# Top.net
KiCad netlist of a schematic drawn in Altium Designer
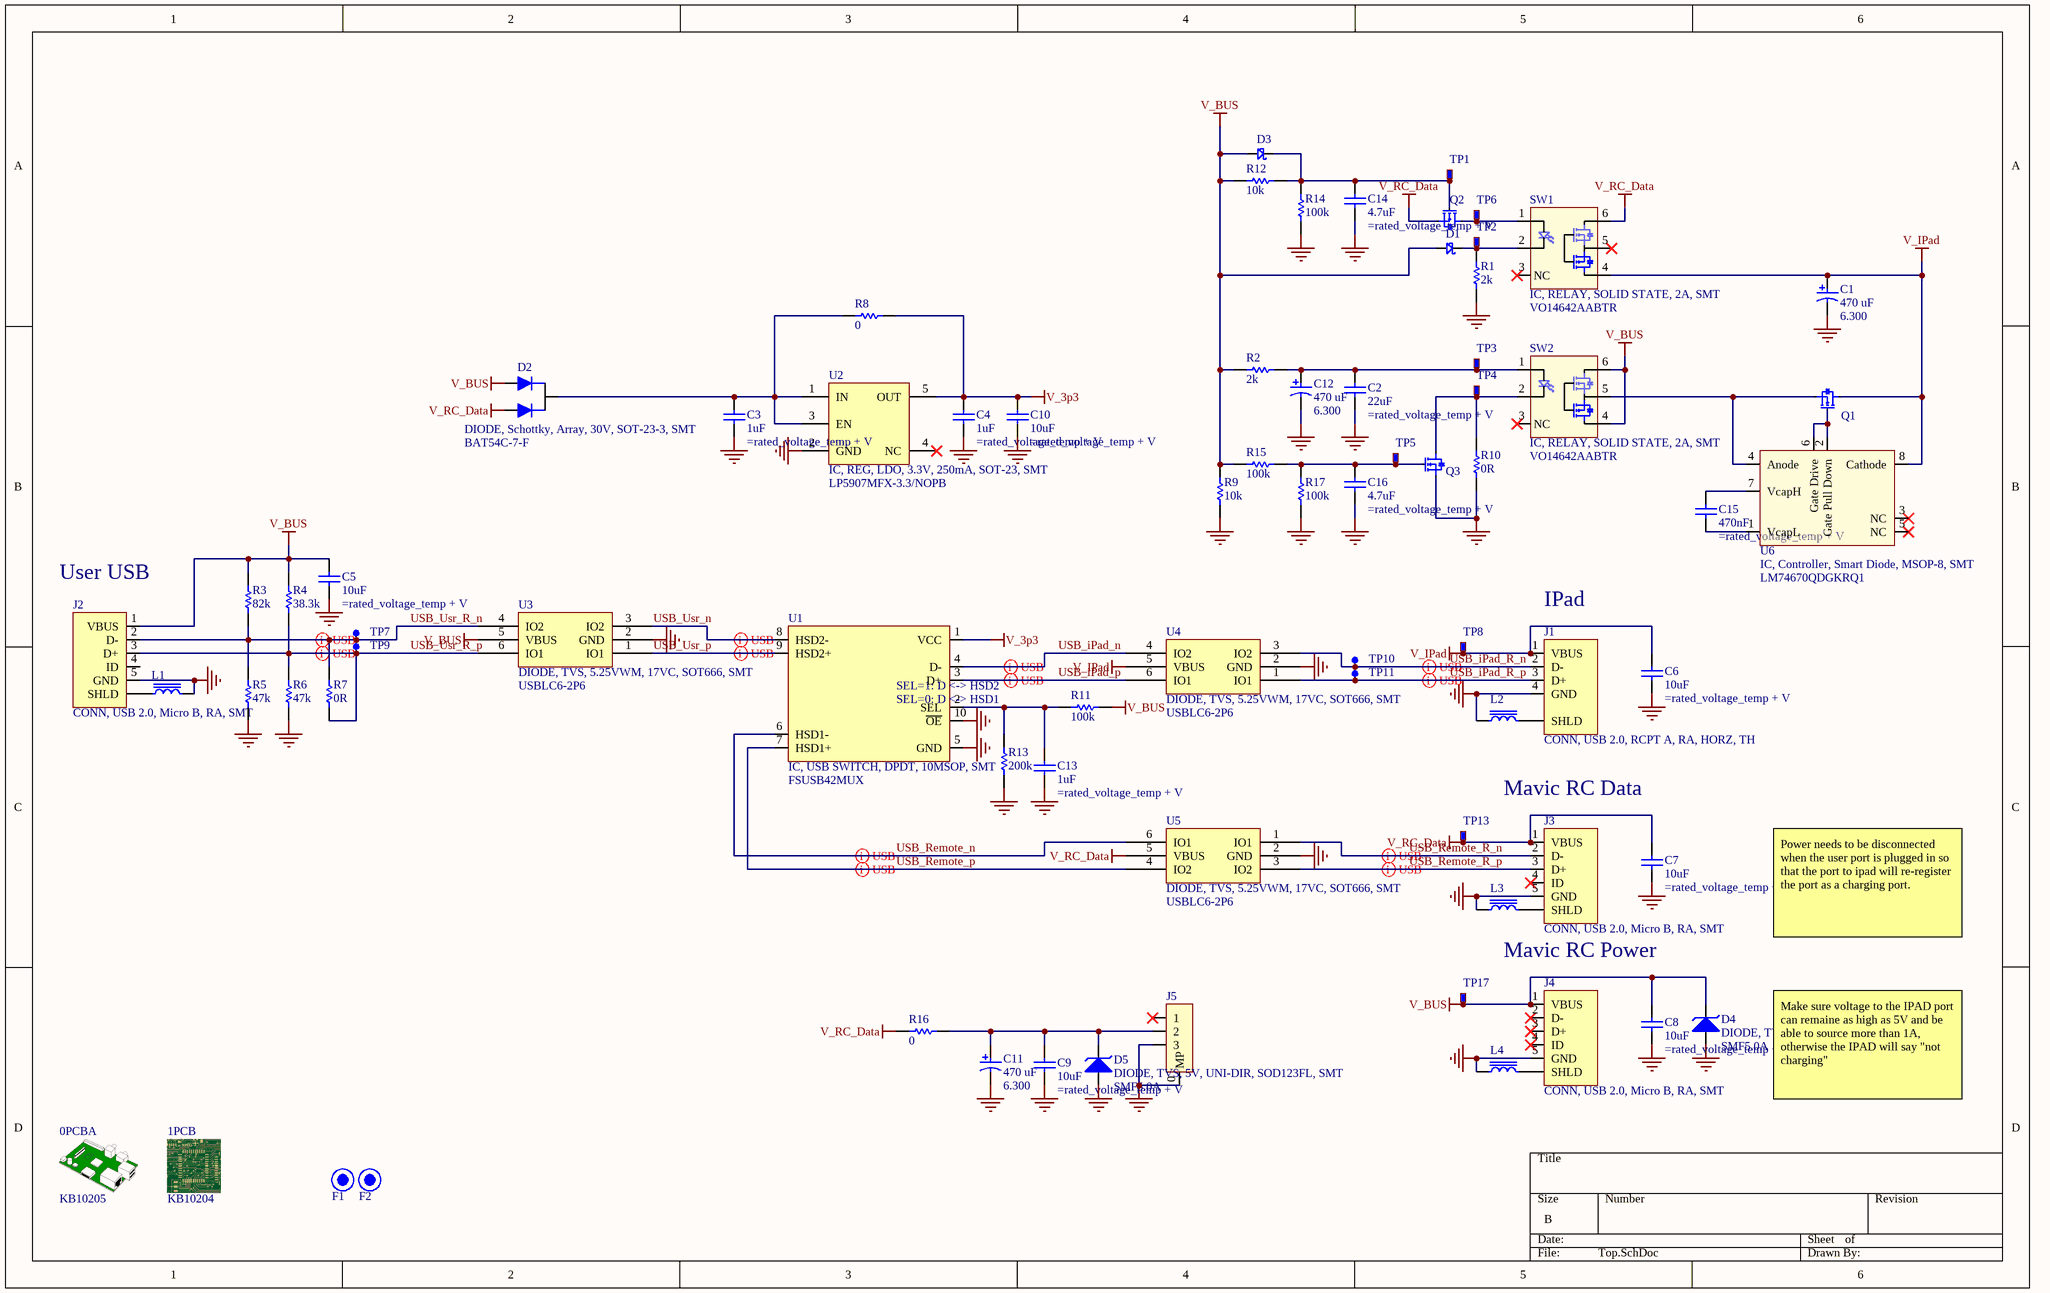
[diagram p0: Top.SchDoc]

(export (version "E")
  (design (tool "Eeschema 10.0.6"))
  (components
    (comp (ref "0PCBA")
      (value "PCBA Schematic Symbol")
      (description "Used for importing Altium BOMs.")
      (fields (field (name "PART_NUMBER") "KH10554"))
      (libsource (lib "kespry") (part "PCBA"))
    )
    (comp (ref "1PCB")
      (value "PCB Schematic Symbol")
      (description "Used for importing Altium BOMs.")
      (fields (field (name "PART_NUMBER") "KH10553"))
      (libsource (lib "kespry") (part "PCB"))
    )
    (comp (ref "C1")
      (value "470 uF")
      (footprint "T520W477M006ATE035")
      (fields
        (field (name "VOLTAGE") "6.300")
        (field (name "PART_NUMBER") "KH10972")
        (field (name "Comment") "CAP, 470uF, TANT POLY, 6.3V, ±20%, 2917, SMT")
      )
      (libsource (lib "kespry") (part "CAP_POL"))
    )
    (comp (ref "C2")
      (value "22uF")
      (footprint "CAPC1206(3216)190_L")
      (description "...")
      (fields (field (name "VOLTAGE") "25.000") (field (name "PART_NUMBER") "KH10501"))
      (libsource (lib "kespry") (part "CAP"))
    )
    (comp (ref "C3")
      (value "1uF")
      (footprint "CAPC0603(1608)100_L")
      (description "...")
      (fields (field (name "VOLTAGE") "50.000") (field (name "PART_NUMBER") "KH10492"))
      (libsource (lib "kespry") (part "CAP"))
    )
    (comp (ref "C4")
      (value "1uF")
      (footprint "CAPC0603(1608)100_L")
      (description "...")
      (fields (field (name "VOLTAGE") "50.000") (field (name "PART_NUMBER") "KH10492"))
      (libsource (lib "kespry") (part "CAP"))
    )
    (comp (ref "C5")
      (value "10uF")
      (footprint "CAPC0603(1608)100_L")
      (description "...")
      (fields (field (name "VOLTAGE") "10.000") (field (name "PART_NUMBER") "KH10478"))
      (libsource (lib "kespry") (part "CAP"))
    )
    (comp (ref "C6")
      (value "10uF")
      (footprint "CAPC0603(1608)100_L")
      (description "...")
      (fields (field (name "VOLTAGE") "10.000") (field (name "PART_NUMBER") "KH10478"))
      (libsource (lib "kespry") (part "CAP"))
    )
    (comp (ref "C7")
      (value "10uF")
      (footprint "CAPC0603(1608)100_L")
      (description "...")
      (fields (field (name "VOLTAGE") "10.000") (field (name "PART_NUMBER") "KH10478"))
      (libsource (lib "kespry") (part "CAP"))
    )
    (comp (ref "C8")
      (value "10uF")
      (footprint "CAPC0603(1608)100_L")
      (description "...")
      (fields (field (name "VOLTAGE") "10.000") (field (name "PART_NUMBER") "KH10478"))
      (libsource (lib "kespry") (part "CAP"))
    )
    (comp (ref "C9")
      (value "10uF")
      (footprint "CAPC0603(1608)100_L")
      (description "...")
      (fields (field (name "VOLTAGE") "10.000") (field (name "PART_NUMBER") "KH10478"))
      (libsource (lib "kespry") (part "CAP"))
    )
    (comp (ref "C10")
      (value "10uF")
      (footprint "CAPC0603(1608)100_L")
      (description "...")
      (fields (field (name "VOLTAGE") "10.000") (field (name "PART_NUMBER") "KH10478"))
      (libsource (lib "kespry") (part "CAP"))
    )
    (comp (ref "C11")
      (value "470 uF")
      (footprint "T520W477M006ATE035")
      (fields
        (field (name "VOLTAGE") "6.300")
        (field (name "PART_NUMBER") "KH10972")
        (field (name "Comment") "CAP, 470uF, TANT POLY, 6.3V, ±20%, 2917, SMT")
      )
      (libsource (lib "kespry") (part "CAP_POL"))
    )
    (comp (ref "C12")
      (value "470 uF")
      (footprint "T520W477M006ATE035")
      (fields
        (field (name "VOLTAGE") "6.300")
        (field (name "PART_NUMBER") "KH10972")
        (field (name "Comment") "CAP, 470uF, TANT POLY, 6.3V, ±20%, 2917, SMT")
      )
      (libsource (lib "kespry") (part "CAP_POL"))
    )
    (comp (ref "C13")
      (value "1uF")
      (footprint "CAPC0603(1608)100_N")
      (description "...")
      (fields (field (name "VOLTAGE") "50.000") (field (name "PART_NUMBER") "KH10492"))
      (libsource (lib "kespry") (part "CAP"))
    )
    (comp (ref "C14")
      (value "4.7uF")
      (footprint "CAPC0603(1608)100_L")
      (description "...")
      (fields (field (name "VOLTAGE") "25.000") (field (name "PART_NUMBER") "KH10511"))
      (libsource (lib "kespry") (part "CAP"))
    )
    (comp (ref "C15")
      (value "470nF")
      (footprint "CAPC0603(1608)100_L")
      (description "...")
      (fields (field (name "VOLTAGE") "25.000") (field (name "PART_NUMBER") "KH10515"))
      (libsource (lib "kespry") (part "CAP"))
    )
    (comp (ref "C16")
      (value "4.7uF")
      (footprint "CAPC0603(1608)100_L")
      (description "...")
      (fields (field (name "VOLTAGE") "25.000") (field (name "PART_NUMBER") "KH10511"))
      (libsource (lib "kespry") (part "CAP"))
    )
    (comp (ref "D1")
      (value "DIODE, Schottky, 45V, 0.1A, SOD323, SMT")
      (footprint "SOD323")
      (description "..")
      (fields (field (name "PART_NUMBER") "KH10397"))
      (libsource (lib "kespry") (part "DIODE_SCHOTTKY"))
    )
    (comp (ref "D2")
      (value "DIODE, Schottky, Array, 30V, SOT-23-3, SMT")
      (footprint "SOT-23-3")
      (fields
        (field (name "PART_NAME") "DIODE, Schottky, Array, 30V, SOT-23-3, SMT")
        (field (name "PART_NUMBER") "KH10976")
        (field (name "MANUFACTURER_PART_NUMBER1") "BAT54C-7-F")
      )
      (libsource (lib "kespry") (part "DIODE_ARRAY_COM_CAT"))
    )
    (comp (ref "D3")
      (value "DIODE, Schottky, 45V, 0.1A, SOD323, SMT")
      (footprint "SOD323")
      (description "..")
      (fields (field (name "PART_NUMBER") "KH10397"))
      (libsource (lib "kespry") (part "DIODE_SCHOTTKY"))
    )
    (comp (ref "D4")
      (value "DIODE, TVS, 5V, UNI-DIR, SOD123FL, SMT")
      (footprint "SOD-123FL")
      (fields
        (field (name "PART_NAME") "DIODE, TVS, 5V, UNI-DIR, SOD123FL, SMT")
        (field (name "PART_NUMBER") "KH10968")
        (field (name "MANUFACTURER_PART_NUMBER1") "SMF5.0A")
      )
      (libsource (lib "kespry") (part "DIODE_TVS_UNI"))
    )
    (comp (ref "D5")
      (value "DIODE, TVS, 5V, UNI-DIR, SOD123FL, SMT")
      (footprint "SOD-123FL")
      (fields
        (field (name "PART_NAME") "DIODE, TVS, 5V, UNI-DIR, SOD123FL, SMT")
        (field (name "PART_NUMBER") "KH10968")
        (field (name "MANUFACTURER_PART_NUMBER1") "SMF5.0A")
      )
      (libsource (lib "kespry") (part "DIODE_TVS_UNI"))
    )
    (comp (ref "F1")
      (value "Fiducial")
      (footprint "FID0.6MM")
      (description "...")
      (fields (field (name "PART_NUMBER") "KH10246"))
      (libsource (lib "kespry") (part "FID"))
    )
    (comp (ref "F2")
      (value "Fiducial")
      (footprint "FID0.6MM")
      (description "...")
      (fields (field (name "PART_NUMBER") "KH10246"))
      (libsource (lib "kespry") (part "FID"))
    )
    (comp (ref "J1")
      (value "CONN, USB 2.0, RCPT A, RA, HORZ, TH")
      (footprint "UE27AC54100")
      (fields
        (field (name "PART_NAME") "CONN, USB 2.0, RCPT A, RA, HORZ, TH")
        (field (name "PART_NUMBER") "KH10969")
      )
      (libsource (lib "kespry") (part "USB_Type_A"))
    )
    (comp (ref "J2")
      (value "CONN, USB 2.0, Micro B, RA, SMT")
      (footprint "10118194-0001LF")
      (description ".")
      (fields
        (field (name "PART_NAME") "CONN, USB 2.0, Micro B, RA, SMT")
        (field (name "PART_NUMBER") "KH10298")
      )
      (libsource (lib "kespry") (part "10118194-0001LF"))
    )
    (comp (ref "J3")
      (value "CONN, USB 2.0, Micro B, RA, SMT")
      (footprint "10118194-0001LF")
      (description ".")
      (fields
        (field (name "PART_NAME") "CONN, USB 2.0, Micro B, RA, SMT")
        (field (name "PART_NUMBER") "KH10298")
      )
      (libsource (lib "") (part "10118194-0001LF_1"))
    )
    (comp (ref "J4")
      (value "CONN, USB 2.0, Micro B, RA, SMT")
      (footprint "10118194-0001LF")
      (description ".")
      (fields
        (field (name "PART_NAME") "CONN, USB 2.0, Micro B, RA, SMT")
        (field (name "PART_NUMBER") "KH10298")
      )
      (libsource (lib "") (part "10118194-0001LF_1"))
    )
    (comp (ref "J5")
      (value "CONN, Header, 3-Pos, Shrouded, 1.25mm Pitch, RA, SMT")
      (footprint "0532610371")
      (fields (field (name "PART_NUMBER") "KH10793"))
      (libsource (lib "kespry") (part "CONN3"))
    )
    (comp (ref "L1")
      (value "FERRITE, 80 OHM, 0402")
      (footprint "IND 1005 (0402)")
      (description "..")
      (fields (field (name "PART_NUMBER") "KH10117"))
      (libsource (lib "kespry") (part "FERRITE"))
    )
    (comp (ref "L2")
      (value "FERRITE, 80 OHM, 0402")
      (footprint "IND 1005 (0402)")
      (description "..")
      (fields (field (name "PART_NUMBER") "KH10117"))
      (libsource (lib "") (part "FERRITE_1"))
    )
    (comp (ref "L3")
      (value "FERRITE, 80 OHM, 0402")
      (footprint "IND 1005 (0402)")
      (description "..")
      (fields (field (name "PART_NUMBER") "KH10117"))
      (libsource (lib "") (part "FERRITE_1"))
    )
    (comp (ref "L4")
      (value "FERRITE, 80 OHM, 0402")
      (footprint "IND 1005 (0402)")
      (description "..")
      (fields (field (name "PART_NUMBER") "KH10117"))
      (libsource (lib "") (part "FERRITE_1"))
    )
    (comp (ref "Q1")
      (value "MOSFET, N-CH, 30V, 6.2A, SOT23")
      (footprint "SOT-23-3")
      (fields (field (name "PART_NUMBER") "KH10792"))
      (libsource (lib "kespry") (part "NFET"))
    )
    (comp (ref "Q2")
      (value "MOSFET, P-CH, 60V, 180mA, SOT-23")
      (footprint "SOT-23-3")
      (description "..")
      (fields (field (name "PART_NUMBER") "KH10356"))
      (libsource (lib "kespry") (part "PFET"))
    )
    (comp (ref "Q3")
      (value "MOSFET, N-CH, 30V, 6.2A, SOT23")
      (footprint "SOT-23-3")
      (fields (field (name "PART_NUMBER") "KH10792"))
      (libsource (lib "kespry") (part "NFET"))
    )
    (comp (ref "R1")
      (value "2k")
      (footprint "RESC0402(1005)_L")
      (description ". .")
      (fields
        (field (name "PART_NUMBER") "KH10444")
        (field (name "Comment") "RES, 2K, 0.063W, 1%, 0402, SMT")
      )
      (libsource (lib "kespry") (part "RES"))
    )
    (comp (ref "R2")
      (value "2k")
      (footprint "RESC0402(1005)_L")
      (description ". .")
      (fields
        (field (name "PART_NUMBER") "KH10444")
        (field (name "Comment") "RES, 2K, 0.063W, 1%, 0402, SMT")
      )
      (libsource (lib "kespry") (part "RES"))
    )
    (comp (ref "R3")
      (value "82k")
      (footprint "RESC0402(1005)_N")
      (fields
        (field (name "PART_NUMBER") "KH10891")
        (field (name "Comment") "RES, 82K, 0.063W, 1%, 0402, SMT")
      )
      (libsource (lib "kespry") (part "RES"))
    )
    (comp (ref "R4")
      (value "38.3k")
      (footprint "RESC0402(1005)_N")
      (fields
        (field (name "PART_NUMBER") "KH10977")
        (field (name "Comment") "RES, 38.3K OHM, 1%, 1/16W, 0402, SMD")
      )
      (libsource (lib "kespry") (part "RES"))
    )
    (comp (ref "R5")
      (value "47k")
      (footprint "RESC0402(1005)_N")
      (description ".")
      (fields
        (field (name "PART_NUMBER") "KH10805")
        (field (name "Comment") "RES, 47K OHM, 1%, 1/5W, 0402, SMD")
      )
      (libsource (lib "kespry") (part "RES"))
    )
    (comp (ref "R6")
      (value "47k")
      (footprint "RESC0402(1005)_N")
      (description ".")
      (fields
        (field (name "PART_NUMBER") "KH10805")
        (field (name "Comment") "RES, 47K OHM, 1%, 1/5W, 0402, SMD")
      )
      (libsource (lib "kespry") (part "RES"))
    )
    (comp (ref "R7")
      (value "0R")
      (footprint "RESC0402(1005)_N")
      (description ".")
      (fields
        (field (name "PART_NUMBER") "KH10412")
        (field (name "Comment") "RES, Jumper, 0R, 0.063W, 0402, SMT")
      )
      (libsource (lib "kespry") (part "RES"))
    )
    (comp (ref "R8")
      (value "0")
      (footprint "RESC0603(1608)_N")
      (fields (field (name "PART_NUMBER") "KH10965") (field (name "Comment") "RES, 0, 0.1W, 1%, 0603, SMT"))
      (libsource (lib "kespry") (part "RES"))
    )
    (comp (ref "R9")
      (value "10k")
      (footprint "RESC0402(1005)_L")
      (description ". .")
      (fields
        (field (name "PART_NUMBER") "KH10420")
        (field (name "Comment") "RES, 10K, 0.063W, 1%, 0402, SMT")
      )
      (libsource (lib "kespry") (part "RES"))
    )
    (comp (ref "R10")
      (value "0R")
      (footprint "RESC0402(1005)_L")
      (description ".")
      (fields
        (field (name "PART_NUMBER") "KH10412")
        (field (name "Comment") "RES, Jumper, 0R, 0.063W, 0402, SMT")
      )
      (libsource (lib "kespry") (part "RES"))
    )
    (comp (ref "R11")
      (value "100k")
      (footprint "RESC0402(1005)_L")
      (description ". .")
      (fields
        (field (name "PART_NUMBER") "KH10416")
        (field (name "Comment") "RES, 100K, 0.063W, 1%, 0402, SMT")
      )
      (libsource (lib "kespry") (part "RES"))
    )
    (comp (ref "R12")
      (value "10k")
      (footprint "RESC0402(1005)_L")
      (description ". .")
      (fields
        (field (name "PART_NUMBER") "KH10420")
        (field (name "Comment") "RES, 10K, 0.063W, 1%, 0402, SMT")
      )
      (libsource (lib "kespry") (part "RES"))
    )
    (comp (ref "R13")
      (value "200k")
      (footprint "RESC0402(1005)_N")
      (description ". .")
      (fields
        (field (name "PART_NUMBER") "KH10438")
        (field (name "Comment") "RES, 200K, 0.063W, 1%, 0402, SMT")
      )
      (libsource (lib "kespry") (part "RES"))
    )
    (comp (ref "R14")
      (value "100k")
      (footprint "RESC0402(1005)_L")
      (description ". .")
      (fields
        (field (name "PART_NUMBER") "KH10416")
        (field (name "Comment") "RES, 100K, 0.063W, 1%, 0402, SMT")
      )
      (libsource (lib "kespry") (part "RES"))
    )
    (comp (ref "R15")
      (value "100k")
      (footprint "RESC0402(1005)_L")
      (description ". .")
      (fields
        (field (name "PART_NUMBER") "KH10416")
        (field (name "Comment") "RES, 100K, 0.063W, 1%, 0402, SMT")
      )
      (libsource (lib "kespry") (part "RES"))
    )
    (comp (ref "R16")
      (value "0")
      (footprint "RESC0603(1608)_N")
      (fields (field (name "PART_NUMBER") "KH10965") (field (name "Comment") "RES, 0, 0.1W, 1%, 0603, SMT"))
      (libsource (lib "kespry") (part "RES"))
    )
    (comp (ref "R17")
      (value "100k")
      (footprint "RESC0402(1005)_L")
      (description ". .")
      (fields
        (field (name "PART_NUMBER") "KH10416")
        (field (name "Comment") "RES, 100K, 0.063W, 1%, 0402, SMT")
      )
      (libsource (lib "kespry") (part "RES"))
    )
    (comp (ref "SW1")
      (value "IC, RELAY, SOLID STATE, 2A, SMT")
      (footprint "VO14642AABTR")
      (fields
        (field (name "PART_NAME") "IC, RELAY, SOLID STATE, 2A, SMT")
        (field (name "PART_NUMBER") "KH10967")
        (field (name "MANUFACTURER_PART_NUMBER1") "VO14642AABTR")
      )
      (libsource (lib "kespry") (part "VO14642AABTR"))
    )
    (comp (ref "SW2")
      (value "IC, RELAY, SOLID STATE, 2A, SMT")
      (footprint "VO14642AABTR")
      (fields
        (field (name "PART_NAME") "IC, RELAY, SOLID STATE, 2A, SMT")
        (field (name "PART_NUMBER") "KH10967")
        (field (name "MANUFACTURER_PART_NUMBER1") "VO14642AABTR")
      )
      (libsource (lib "kespry") (part "VO14642AABTR"))
    )
    (comp (ref "TP1")
      (value "TESTPOINT, 0603, SMT")
      (footprint "TP0603")
      (description "..")
      (fields (field (name "PART_NUMBER") "KH10245"))
      (libsource (lib "kespry") (part "TP_RECT"))
    )
    (comp (ref "TP2")
      (value "TESTPOINT, 0603, SMT")
      (footprint "TP0603")
      (description "..")
      (fields (field (name "PART_NUMBER") "KH10245"))
      (libsource (lib "kespry") (part "TP_RECT"))
    )
    (comp (ref "TP3")
      (value "TESTPOINT, 0603, SMT")
      (footprint "TP0603")
      (description "..")
      (fields (field (name "PART_NUMBER") "KH10245"))
      (libsource (lib "kespry") (part "TP_RECT"))
    )
    (comp (ref "TP4")
      (value "TESTPOINT, 0603, SMT")
      (footprint "TP0603")
      (description "..")
      (fields (field (name "PART_NUMBER") "KH10245"))
      (libsource (lib "kespry") (part "TP_RECT"))
    )
    (comp (ref "TP5")
      (value "TESTPOINT, 0603, SMT")
      (footprint "TP0603")
      (description "..")
      (fields (field (name "PART_NUMBER") "KH10245"))
      (libsource (lib "kespry") (part "TP_RECT"))
    )
    (comp (ref "TP6")
      (value "TESTPOINT, 0603, SMT")
      (footprint "TP0603")
      (description "..")
      (fields (field (name "PART_NUMBER") "KH10245"))
      (libsource (lib "kespry") (part "TP_RECT"))
    )
    (comp (ref "TP7")
      (value "TESTPOINT, 1mm Diam, Round")
      (footprint "TP1MM")
      (description "...")
      (fields (field (name "PART_NUMBER") "KH10379"))
      (libsource (lib "kespry") (part "TP"))
    )
    (comp (ref "TP8")
      (value "TESTPOINT, 0603, SMT")
      (footprint "TP0603")
      (description "..")
      (fields (field (name "PART_NUMBER") "KH10245"))
      (libsource (lib "kespry") (part "TP_RECT"))
    )
    (comp (ref "TP9")
      (value "TESTPOINT, 1mm Diam, Round")
      (footprint "TP1MM")
      (description "...")
      (fields (field (name "PART_NUMBER") "KH10379"))
      (libsource (lib "kespry") (part "TP"))
    )
    (comp (ref "TP10")
      (value "TESTPOINT, 1mm Diam, Round")
      (footprint "TP1MM")
      (description "...")
      (fields (field (name "PART_NUMBER") "KH10379"))
      (libsource (lib "kespry") (part "TP"))
    )
    (comp (ref "TP11")
      (value "TESTPOINT, 1mm Diam, Round")
      (footprint "TP1MM")
      (description "...")
      (fields (field (name "PART_NUMBER") "KH10379"))
      (libsource (lib "kespry") (part "TP"))
    )
    (comp (ref "TP13")
      (value "TESTPOINT, 0603, SMT")
      (footprint "TP0603")
      (description "..")
      (fields (field (name "PART_NUMBER") "KH10245"))
      (libsource (lib "kespry") (part "TP_RECT"))
    )
    (comp (ref "TP17")
      (value "TESTPOINT, 0603, SMT")
      (footprint "TP0603")
      (description "..")
      (fields (field (name "PART_NUMBER") "KH10245"))
      (libsource (lib "kespry") (part "TP_RECT"))
    )
    (comp (ref "U1")
      (value "IC, USB SWITCH, DPDT, 10MSOP, SMT")
      (footprint "MSOP10")
      (fields
        (field (name "PART_NAME") "IC, USB SWITCH, DPDT, 10MSOP, SMT")
        (field (name "PART_NUMBER") "KH10970")
        (field (name "MANUFACTURER_PART_NUMBER1") "FSUSB42MUX")
      )
      (libsource (lib "kespry") (part "FSUSB42MUX"))
    )
    (comp (ref "U2")
      (value "IC, REG, LDO, 3.3V, 250mA, SOT-23, SMT")
      (footprint "DBV (SOT-23)")
      (description "..")
      (fields
        (field (name "PART_NAME") "IC, REG, LDO, 3.3V, 250mA, SOT-23, SMT")
        (field (name "PART_NUMBER") "KH10237")
        (field (name "MANUFACTURER_PART_NUMBER1") "LP5907MFX-3.3/NOPB")
      )
      (libsource (lib "kespry") (part "LP5907MFX-3.3"))
    )
    (comp (ref "U3")
      (value "DIODE, TVS, 5.25VWM, 17VC, SOT666, SMT")
      (footprint "SOT-666")
      (description "..")
      (fields
        (field (name "PART_NAME") "DIODE, TVS, 5.25VWM, 17VC, SOT666, SMT")
        (field (name "PART_NUMBER") "KH10130")
        (field (name "MANUFACTURER_PART_NUMBER1") "USBLC6-2P6")
      )
      (libsource (lib "") (part "USBLC6-2P6_1"))
    )
    (comp (ref "U4")
      (value "DIODE, TVS, 5.25VWM, 17VC, SOT666, SMT")
      (footprint "SOT-666")
      (description "..")
      (fields
        (field (name "PART_NAME") "DIODE, TVS, 5.25VWM, 17VC, SOT666, SMT")
        (field (name "PART_NUMBER") "KH10130")
        (field (name "MANUFACTURER_PART_NUMBER1") "USBLC6-2P6")
      )
      (libsource (lib "") (part "USBLC6-2P6_1"))
    )
    (comp (ref "U5")
      (value "DIODE, TVS, 5.25VWM, 17VC, SOT666, SMT")
      (footprint "SOT-666")
      (description "..")
      (fields
        (field (name "PART_NAME") "DIODE, TVS, 5.25VWM, 17VC, SOT666, SMT")
        (field (name "PART_NUMBER") "KH10130")
        (field (name "MANUFACTURER_PART_NUMBER1") "USBLC6-2P6")
      )
      (libsource (lib "kespry") (part "USBLC6-2P6"))
    )
    (comp (ref "U6")
      (value "IC, Controller, Smart Diode, MSOP-8, SMT")
      (footprint "MSOP8")
      (fields
        (field (name "PART_NAME") "IC, Controller, Smart Diode, MSOP-8, SMT")
        (field (name "PART_NUMBER") "KH10944")
        (field (name "MANUFACTURER_PART_NUMBER1") "LM74670QDGKRQ1")
      )
      (libsource (lib "kespry") (part "LM74670-Q1"))
    )
  )
  (nets
    (net (code "1") (name "/USB_Remote_R_n") (class "Default")
      (node (ref "J3") (pin "2") (pinfunction "D-_2") (pintype "bidirectional"))
      (node (ref "U5") (pin "1") (pinfunction "IO1_1") (pintype "passive"))
    )
    (net (code "2") (name "/USB_Remote_R_p") (class "Default")
      (node (ref "J3") (pin "3") (pinfunction "D+_3") (pintype "bidirectional"))
      (node (ref "U5") (pin "3") (pinfunction "IO2_3") (pintype "passive"))
    )
    (net (code "3") (name "/USB_Remote_n") (class "Default")
      (node (ref "U1") (pin "6") (pinfunction "HSD1-_6") (pintype "passive"))
      (node (ref "U5") (pin "6") (pinfunction "IO1_6") (pintype "passive"))
    )
    (net (code "4") (name "/USB_Remote_p") (class "Default")
      (node (ref "U1") (pin "7") (pinfunction "HSD1+_7") (pintype "passive"))
      (node (ref "U5") (pin "4") (pinfunction "IO2_4") (pintype "passive"))
    )
    (net (code "5") (name "/USB_Usr_R_n") (class "Default")
      (node (ref "J2") (pin "2") (pinfunction "D-_2") (pintype "bidirectional"))
      (node (ref "R3") (pin "1") (pinfunction "1_1") (pintype "passive"))
      (node (ref "R5") (pin "2") (pinfunction "2_2") (pintype "passive"))
      (node (ref "R7") (pin "2") (pinfunction "2_2") (pintype "passive"))
      (node (ref "TP7") (pin "1") (pinfunction "1_1") (pintype "passive"))
      (node (ref "U3") (pin "4") (pinfunction "IO2_4") (pintype "passive"))
    )
    (net (code "6") (name "/USB_Usr_R_p") (class "Default")
      (node (ref "J2") (pin "3") (pinfunction "D+_3") (pintype "bidirectional"))
      (node (ref "R4") (pin "1") (pinfunction "1_1") (pintype "passive"))
      (node (ref "R6") (pin "2") (pinfunction "2_2") (pintype "passive"))
      (node (ref "R7") (pin "1") (pinfunction "1_1") (pintype "passive"))
      (node (ref "TP9") (pin "1") (pinfunction "1_1") (pintype "passive"))
      (node (ref "U3") (pin "6") (pinfunction "IO1_6") (pintype "passive"))
    )
    (net (code "7") (name "/USB_Usr_n") (class "Default")
      (node (ref "U1") (pin "8") (pinfunction "HSD2-_8") (pintype "passive"))
      (node (ref "U3") (pin "3") (pinfunction "IO2_3") (pintype "passive"))
    )
    (net (code "8") (name "/USB_Usr_p") (class "Default")
      (node (ref "U1") (pin "9") (pinfunction "HSD2+_9") (pintype "passive"))
      (node (ref "U3") (pin "1") (pinfunction "IO1_1") (pintype "passive"))
    )
    (net (code "9") (name "/USB_iPad_R_n") (class "Default")
      (node (ref "J1") (pin "2") (pinfunction "D-_2") (pintype "bidirectional"))
      (node (ref "TP10") (pin "1") (pinfunction "1_1") (pintype "passive"))
      (node (ref "U4") (pin "3") (pinfunction "IO2_3") (pintype "passive"))
    )
    (net (code "10") (name "/USB_iPad_R_p") (class "Default")
      (node (ref "J1") (pin "3") (pinfunction "D+_3") (pintype "bidirectional"))
      (node (ref "TP11") (pin "1") (pinfunction "1_1") (pintype "passive"))
      (node (ref "U4") (pin "1") (pinfunction "IO1_1") (pintype "passive"))
    )
    (net (code "11") (name "/USB_iPad_n") (class "Default")
      (node (ref "U1") (pin "4") (pinfunction "D-_4") (pintype "passive"))
      (node (ref "U4") (pin "4") (pinfunction "IO2_4") (pintype "passive"))
    )
    (net (code "12") (name "/USB_iPad_p") (class "Default")
      (node (ref "U1") (pin "3") (pinfunction "D+_3") (pintype "passive"))
      (node (ref "U4") (pin "6") (pinfunction "IO1_6") (pintype "passive"))
    )
    (net (code "13") (name "GND") (class "Default")
      (node (ref "C1") (pin "2") (pinfunction "2_2") (pintype "passive"))
      (node (ref "C10") (pin "2") (pinfunction "2_2") (pintype "passive"))
      (node (ref "C11") (pin "2") (pinfunction "2_2") (pintype "passive"))
      (node (ref "C12") (pin "2") (pinfunction "2_2") (pintype "passive"))
      (node (ref "C13") (pin "2") (pinfunction "2_2") (pintype "passive"))
      (node (ref "C14") (pin "2") (pinfunction "2_2") (pintype "passive"))
      (node (ref "C16") (pin "2") (pinfunction "2_2") (pintype "passive"))
      (node (ref "C2") (pin "2") (pinfunction "2_2") (pintype "passive"))
      (node (ref "C3") (pin "2") (pinfunction "2_2") (pintype "passive"))
      (node (ref "C4") (pin "2") (pinfunction "2_2") (pintype "passive"))
      (node (ref "C5") (pin "2") (pinfunction "2_2") (pintype "passive"))
      (node (ref "C6") (pin "2") (pinfunction "2_2") (pintype "passive"))
      (node (ref "C7") (pin "2") (pinfunction "2_2") (pintype "passive"))
      (node (ref "C8") (pin "2") (pinfunction "2_2") (pintype "passive"))
      (node (ref "C9") (pin "2") (pinfunction "2_2") (pintype "passive"))
      (node (ref "D4") (pin "2") (pinfunction "2_2") (pintype "passive"))
      (node (ref "D5") (pin "2") (pinfunction "2_2") (pintype "passive"))
      (node (ref "J1") (pin "4") (pinfunction "GND_4") (pintype "power_in"))
      (node (ref "J2") (pin "5") (pinfunction "GND_5") (pintype "power_in"))
      (node (ref "J3") (pin "5") (pinfunction "GND_5") (pintype "power_in"))
      (node (ref "J4") (pin "5") (pinfunction "GND_5") (pintype "power_in"))
      (node (ref "J5") (pin "0") (pinfunction "MP_0") (pintype "passive"))
      (node (ref "J5") (pin "3") (pinfunction "3_3") (pintype "passive"))
      (node (ref "L1") (pin "1") (pinfunction "1_1") (pintype "passive"))
      (node (ref "L2") (pin "1") (pinfunction "1_1") (pintype "passive"))
      (node (ref "L3") (pin "1") (pinfunction "1_1") (pintype "passive"))
      (node (ref "L4") (pin "1") (pinfunction "1_1") (pintype "passive"))
      (node (ref "Q3") (pin "2") (pinfunction "S_2") (pintype "passive"))
      (node (ref "R1") (pin "2") (pinfunction "2_2") (pintype "passive"))
      (node (ref "R10") (pin "1") (pinfunction "1_1") (pintype "passive"))
      (node (ref "R13") (pin "1") (pinfunction "1_1") (pintype "passive"))
      (node (ref "R14") (pin "2") (pinfunction "2_2") (pintype "passive"))
      (node (ref "R17") (pin "2") (pinfunction "2_2") (pintype "passive"))
      (node (ref "R5") (pin "1") (pinfunction "1_1") (pintype "passive"))
      (node (ref "R6") (pin "1") (pinfunction "1_1") (pintype "passive"))
      (node (ref "R9") (pin "2") (pinfunction "2_2") (pintype "passive"))
      (node (ref "U1") (pin "10") (pinfunction "~{OE}_10") (pintype "passive"))
      (node (ref "U1") (pin "5") (pinfunction "GND_5") (pintype "passive"))
      (node (ref "U2") (pin "2") (pinfunction "GND_2") (pintype "passive"))
      (node (ref "U3") (pin "2") (pinfunction "GND_2") (pintype "passive"))
      (node (ref "U4") (pin "2") (pinfunction "GND_2") (pintype "passive"))
      (node (ref "U5") (pin "2") (pinfunction "GND_2") (pintype "passive"))
    )
    (net (code "14") (name "Net-(C11-Pad1)") (class "Default")
      (node (ref "C11") (pin "1") (pinfunction "1_1") (pintype "passive"))
      (node (ref "C9") (pin "1") (pinfunction "1_1") (pintype "passive"))
      (node (ref "D5") (pin "1") (pinfunction "1_1") (pintype "passive"))
      (node (ref "J5") (pin "2") (pinfunction "2_2") (pintype "passive"))
      (node (ref "R16") (pin "2") (pinfunction "2_2") (pintype "passive"))
    )
    (net (code "15") (name "Net-(D2-K)") (class "Default")
      (node (ref "C3") (pin "1") (pinfunction "1_1") (pintype "passive"))
      (node (ref "D2") (pin "3") (pinfunction "K_3") (pintype "passive"))
      (node (ref "R8") (pin "2") (pinfunction "2_2") (pintype "passive"))
      (node (ref "U2") (pin "1") (pinfunction "IN_1") (pintype "passive"))
      (node (ref "U2") (pin "3") (pinfunction "EN_3") (pintype "passive"))
    )
    (net (code "16") (name "Net-(J1-SHLD)") (class "Default")
      (node (ref "J1") (pin "0") (pinfunction "SHLD_0") (pintype "passive"))
      (node (ref "L2") (pin "2") (pinfunction "2_2") (pintype "passive"))
    )
    (net (code "17") (name "Net-(J2-SHLD)") (class "Default")
      (node (ref "J2") (pin "0") (pinfunction "SHLD_0") (pintype "passive"))
      (node (ref "L1") (pin "2") (pinfunction "2_2") (pintype "passive"))
    )
    (net (code "18") (name "Net-(J3-SHLD)") (class "Default")
      (node (ref "J3") (pin "0") (pinfunction "SHLD_0") (pintype "passive"))
      (node (ref "L3") (pin "2") (pinfunction "2_2") (pintype "passive"))
    )
    (net (code "19") (name "Net-(J4-SHLD)") (class "Default")
      (node (ref "J4") (pin "0") (pinfunction "SHLD_0") (pintype "passive"))
      (node (ref "L4") (pin "2") (pinfunction "2_2") (pintype "passive"))
    )
    (net (code "20") (name "Net-(Q1-G)") (class "Default")
      (node (ref "Q1") (pin "1") (pinfunction "G_1") (pintype "passive"))
      (node (ref "U6") (pin "2") (pinfunction "Gate_Pull_Down_2") (pintype "passive"))
      (node (ref "U6") (pin "6") (pinfunction "Gate_Drive_6") (pintype "passive"))
    )
    (net (code "21") (name "Net-(Q1-S)") (class "Default")
      (node (ref "Q1") (pin "2") (pinfunction "S_2") (pintype "passive"))
      (node (ref "SW2") (pin "5") (pinfunction "DC_5") (pintype "passive"))
      (node (ref "U6") (pin "4") (pinfunction "Anode_4") (pintype "passive"))
    )
    (net (code "22") (name "Net-(Q2-D)") (class "Default")
      (node (ref "Q2") (pin "3") (pinfunction "D_3") (pintype "passive"))
      (node (ref "SW1") (pin "1") (pinfunction "Anode_1") (pintype "passive"))
      (node (ref "TP6") (pin "1") (pinfunction "TP_1") (pintype "passive"))
    )
    (net (code "23") (name "Net-(Q2-G)") (class "Default")
      (node (ref "C14") (pin "1") (pinfunction "1_1") (pintype "passive"))
      (node (ref "D3") (pin "2") (pinfunction "2_2") (pintype "passive"))
      (node (ref "Q2") (pin "1") (pinfunction "G_1") (pintype "passive"))
      (node (ref "R12") (pin "1") (pinfunction "1_1") (pintype "passive"))
      (node (ref "R14") (pin "1") (pinfunction "1_1") (pintype "passive"))
      (node (ref "TP1") (pin "1") (pinfunction "TP_1") (pintype "passive"))
    )
    (net (code "24") (name "Net-(Q3-D)") (class "Default")
      (node (ref "Q3") (pin "3") (pinfunction "D_3") (pintype "passive"))
      (node (ref "R10") (pin "2") (pinfunction "2_2") (pintype "passive"))
      (node (ref "SW2") (pin "2") (pinfunction "Cathode_2") (pintype "passive"))
      (node (ref "TP4") (pin "1") (pinfunction "TP_1") (pintype "passive"))
    )
    (net (code "25") (name "Net-(Q3-G)") (class "Default")
      (node (ref "C16") (pin "1") (pinfunction "1_1") (pintype "passive"))
      (node (ref "Q3") (pin "1") (pinfunction "G_1") (pintype "passive"))
      (node (ref "R15") (pin "2") (pinfunction "2_2") (pintype "passive"))
      (node (ref "R17") (pin "1") (pinfunction "1_1") (pintype "passive"))
      (node (ref "TP5") (pin "1") (pinfunction "TP_1") (pintype "passive"))
    )
    (net (code "26") (name "Net-(SW1-Cathode)") (class "Default")
      (node (ref "D1") (pin "2") (pinfunction "2_2") (pintype "passive"))
      (node (ref "R1") (pin "1") (pinfunction "1_1") (pintype "passive"))
      (node (ref "SW1") (pin "2") (pinfunction "Cathode_2") (pintype "passive"))
      (node (ref "TP2") (pin "1") (pinfunction "TP_1") (pintype "passive"))
    )
    (net (code "27") (name "Net-(SW2-Anode)") (class "Default")
      (node (ref "C12") (pin "1") (pinfunction "1_1") (pintype "passive"))
      (node (ref "C2") (pin "1") (pinfunction "1_1") (pintype "passive"))
      (node (ref "R2") (pin "2") (pinfunction "2_2") (pintype "passive"))
      (node (ref "SW2") (pin "1") (pinfunction "Anode_1") (pintype "passive"))
      (node (ref "TP3") (pin "1") (pinfunction "TP_1") (pintype "passive"))
    )
    (net (code "28") (name "Net-(U1-SEL)") (class "Default")
      (node (ref "C13") (pin "1") (pinfunction "1_1") (pintype "passive"))
      (node (ref "R11") (pin "1") (pinfunction "1_1") (pintype "passive"))
      (node (ref "R13") (pin "2") (pinfunction "2_2") (pintype "passive"))
      (node (ref "U1") (pin "2") (pinfunction "SEL_2") (pintype "passive"))
    )
    (net (code "29") (name "Net-(U6-VcapH)") (class "Default")
      (node (ref "C15") (pin "2") (pinfunction "2_2") (pintype "passive"))
      (node (ref "U6") (pin "7") (pinfunction "VcapH_7") (pintype "passive"))
    )
    (net (code "30") (name "Net-(U6-VcapL)") (class "Default")
      (node (ref "C15") (pin "1") (pinfunction "1_1") (pintype "passive"))
      (node (ref "U6") (pin "1") (pinfunction "VcapL_1") (pintype "passive"))
    )
    (net (code "31") (name "V_3p3") (class "Default")
      (node (ref "C10") (pin "1") (pinfunction "1_1") (pintype "passive"))
      (node (ref "C4") (pin "1") (pinfunction "1_1") (pintype "passive"))
      (node (ref "R8") (pin "1") (pinfunction "1_1") (pintype "passive"))
      (node (ref "U1") (pin "1") (pinfunction "VCC_1") (pintype "passive"))
      (node (ref "U2") (pin "5") (pinfunction "OUT_5") (pintype "passive"))
    )
    (net (code "32") (name "V_BUS") (class "Default")
      (node (ref "C5") (pin "1") (pinfunction "1_1") (pintype "passive"))
      (node (ref "C8") (pin "1") (pinfunction "1_1") (pintype "passive"))
      (node (ref "D1") (pin "1") (pinfunction "1_1") (pintype "passive"))
      (node (ref "D2") (pin "1") (pinfunction "A1_1") (pintype "passive"))
      (node (ref "D3") (pin "1") (pinfunction "1_1") (pintype "passive"))
      (node (ref "D4") (pin "1") (pinfunction "1_1") (pintype "passive"))
      (node (ref "J2") (pin "1") (pinfunction "VBUS_1") (pintype "power_in"))
      (node (ref "J4") (pin "1") (pinfunction "VBUS_1") (pintype "power_in"))
      (node (ref "R11") (pin "2") (pinfunction "2_2") (pintype "passive"))
      (node (ref "R12") (pin "2") (pinfunction "2_2") (pintype "passive"))
      (node (ref "R15") (pin "1") (pinfunction "1_1") (pintype "passive"))
      (node (ref "R2") (pin "1") (pinfunction "1_1") (pintype "passive"))
      (node (ref "R3") (pin "2") (pinfunction "2_2") (pintype "passive"))
      (node (ref "R4") (pin "2") (pinfunction "2_2") (pintype "passive"))
      (node (ref "R9") (pin "1") (pinfunction "1_1") (pintype "passive"))
      (node (ref "SW2") (pin "4") (pinfunction "S'_4") (pintype "passive"))
      (node (ref "SW2") (pin "6") (pinfunction "S_6") (pintype "passive"))
      (node (ref "TP17") (pin "1") (pinfunction "TP_1") (pintype "passive"))
      (node (ref "U3") (pin "5") (pinfunction "VBUS_5") (pintype "passive"))
    )
    (net (code "33") (name "V_IPad") (class "Default")
      (node (ref "C1") (pin "1") (pinfunction "1_1") (pintype "passive"))
      (node (ref "C6") (pin "1") (pinfunction "1_1") (pintype "passive"))
      (node (ref "J1") (pin "1") (pinfunction "VBUS_1") (pintype "power_in"))
      (node (ref "Q1") (pin "3") (pinfunction "D_3") (pintype "passive"))
      (node (ref "SW1") (pin "4") (pinfunction "S'_4") (pintype "passive"))
      (node (ref "TP8") (pin "1") (pinfunction "TP_1") (pintype "passive"))
      (node (ref "U4") (pin "5") (pinfunction "VBUS_5") (pintype "passive"))
      (node (ref "U6") (pin "8") (pinfunction "Cathode_8") (pintype "passive"))
    )
    (net (code "34") (name "V_RC_Data") (class "Default")
      (node (ref "C7") (pin "1") (pinfunction "1_1") (pintype "passive"))
      (node (ref "D2") (pin "2") (pinfunction "A2_2") (pintype "passive"))
      (node (ref "J3") (pin "1") (pinfunction "VBUS_1") (pintype "power_in"))
      (node (ref "Q2") (pin "2") (pinfunction "S_2") (pintype "passive"))
      (node (ref "R16") (pin "1") (pinfunction "1_1") (pintype "passive"))
      (node (ref "SW1") (pin "6") (pinfunction "S_6") (pintype "passive"))
      (node (ref "TP13") (pin "1") (pinfunction "TP_1") (pintype "passive"))
      (node (ref "U5") (pin "5") (pinfunction "VBUS_5") (pintype "passive"))
    )
    (net (code "35") (name "unconnected-(J2-ID-Pad4)") (class "Default")
      (node (ref "J2") (pin "4") (pinfunction "ID_4") (pintype "passive"))
    )
    (net (code "36") (name "unconnected-(J3-ID-Pad4)") (class "Default")
      (node (ref "J3") (pin "4") (pinfunction "ID_4") (pintype "passive+no_connect"))
    )
    (net (code "37") (name "unconnected-(J4-D+-Pad3)") (class "Default")
      (node (ref "J4") (pin "3") (pinfunction "D+_3") (pintype "bidirectional+no_connect"))
    )
    (net (code "38") (name "unconnected-(J4-D--Pad2)") (class "Default")
      (node (ref "J4") (pin "2") (pinfunction "D-_2") (pintype "bidirectional+no_connect"))
    )
    (net (code "39") (name "unconnected-(J4-ID-Pad4)") (class "Default")
      (node (ref "J4") (pin "4") (pinfunction "ID_4") (pintype "passive+no_connect"))
    )
    (net (code "40") (name "unconnected-(J5-Pad1)") (class "Default")
      (node (ref "J5") (pin "1") (pinfunction "1_1") (pintype "passive+no_connect"))
    )
    (net (code "41") (name "unconnected-(SW1-DC-Pad5)") (class "Default")
      (node (ref "SW1") (pin "5") (pinfunction "DC_5") (pintype "passive+no_connect"))
    )
    (net (code "42") (name "unconnected-(SW1-NC-Pad3)") (class "Default")
      (node (ref "SW1") (pin "3") (pinfunction "NC_3") (pintype "passive+no_connect"))
    )
    (net (code "43") (name "unconnected-(SW2-NC-Pad3)") (class "Default")
      (node (ref "SW2") (pin "3") (pinfunction "NC_3") (pintype "passive+no_connect"))
    )
    (net (code "44") (name "unconnected-(U2-NC-Pad4)") (class "Default")
      (node (ref "U2") (pin "4") (pinfunction "NC_4") (pintype "passive+no_connect"))
    )
    (net (code "45") (name "unconnected-(U6-NC-Pad3)") (class "Default")
      (node (ref "U6") (pin "3") (pinfunction "NC_3") (pintype "passive+no_connect"))
    )
    (net (code "46") (name "unconnected-(U6-NC-Pad5)") (class "Default")
      (node (ref "U6") (pin "5") (pinfunction "NC_5") (pintype "passive+no_connect"))
    )
  )
)
